# power_stub.net
KiCad netlist of a schematic drawn in EAGLE
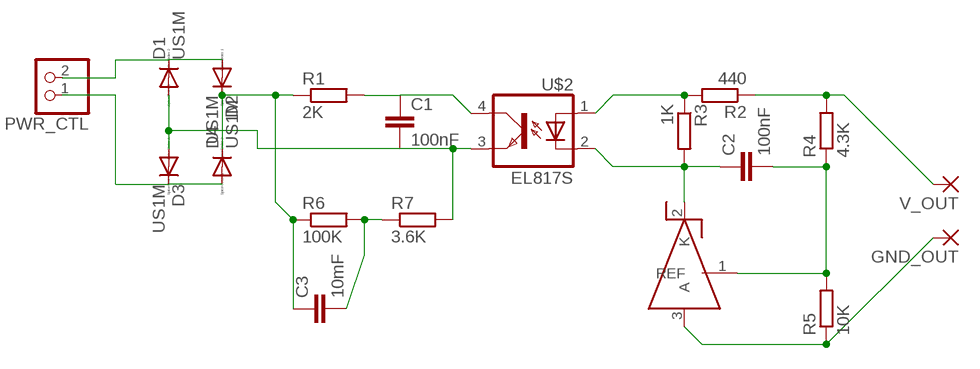
[diagram p0: schematic, sheet 1]

(export (version "E")
  (design (tool "Eeschema 10.0.6"))
  (components
    (comp (ref "C1")
      (value "100nF")
      (footprint "eagle-import:C0805")
      (libsource (lib "eagle-import") (part "C-EUC0805"))
    )
    (comp (ref "C2")
      (value "100nF")
      (footprint "eagle-import:C0805")
      (libsource (lib "eagle-import") (part "resistor_C-EUC0805"))
    )
    (comp (ref "C3")
      (value "10mF")
      (footprint "eagle-import:C0805")
      (libsource (lib "eagle-import") (part "C-EUC0805"))
    )
    (comp (ref "D1")
      (value "US1M")
      (footprint "eagle-import:DO-214AC")
      (libsource (lib "eagle-import") (part "DIODE-DO-214AC"))
    )
    (comp (ref "D2")
      (value "US1M")
      (footprint "eagle-import:DO-214AC")
      (libsource (lib "eagle-import") (part "DIODE-DO-214AC"))
    )
    (comp (ref "D3")
      (value "US1M")
      (footprint "eagle-import:DO-214AC")
      (libsource (lib "eagle-import") (part "DIODE-DO-214AC"))
    )
    (comp (ref "D4")
      (value "US1M")
      (footprint "eagle-import:DO-214AC")
      (libsource (lib "eagle-import") (part "DIODE-DO-214AC"))
    )
    (comp (ref "GND_OUT")
      (value "SMD5")
      (footprint "eagle-import:SMD2,54-5,08")
      (libsource (lib "eagle-import") (part "SMD5"))
    )
    (comp (ref "PWR_CTL")
      (value "PINHD-1X2/90")
      (footprint "eagle-import:1X02_90")
      (libsource (lib "eagle-import") (part "PINHD-1X2/90"))
    )
    (comp (ref "R1")
      (value "2K")
      (footprint "eagle-import:R0805")
      (libsource (lib "eagle-import") (part "R-EU_R0805"))
    )
    (comp (ref "R2")
      (value "440")
      (footprint "eagle-import:R0805")
      (libsource (lib "eagle-import") (part "resistor_R-EU_R0805"))
    )
    (comp (ref "R3")
      (value "1K")
      (footprint "eagle-import:R0805")
      (libsource (lib "eagle-import") (part "resistor_R-EU_R0805"))
    )
    (comp (ref "R4")
      (value "4.3K")
      (footprint "eagle-import:R0805")
      (libsource (lib "eagle-import") (part "resistor_R-EU_R0805"))
    )
    (comp (ref "R5")
      (value "10K")
      (footprint "eagle-import:R0805")
      (libsource (lib "eagle-import") (part "resistor_R-EU_R0805"))
    )
    (comp (ref "R6")
      (value "100K")
      (footprint "eagle-import:R0805")
      (libsource (lib "eagle-import") (part "R-EU_R0805"))
    )
    (comp (ref "R7")
      (value "3.6K")
      (footprint "eagle-import:R0805")
      (libsource (lib "eagle-import") (part "R-EU_R0805"))
    )
    (comp (ref "U$1")
      (value "TL431AIDBZR")
      (footprint "eagle-import:SOT23")
      (libsource (lib "eagle-import") (part "TL431AIDBZR"))
    )
    (comp (ref "U$2")
      (value "EL817S")
      (footprint "eagle-import:SMD4_L")
      (libsource (lib "eagle-import") (part "EL817S"))
    )
    (comp (ref "V_OUT")
      (value "SMD5")
      (footprint "eagle-import:SMD2,54-5,08")
      (libsource (lib "eagle-import") (part "SMD5"))
    )
  )
  (nets
    (net (code "1") (name "Net-(C3-Pad1)") (class "Default")
      (node (ref "C3") (pin "1") (pinfunction "1_1") (pintype "passive"))
      (node (ref "D2") (pin "C") (pinfunction "C_C") (pintype "passive"))
      (node (ref "D4") (pin "C") (pinfunction "C_C") (pintype "passive"))
      (node (ref "R1") (pin "1") (pinfunction "1_1") (pintype "passive"))
      (node (ref "R6") (pin "1") (pinfunction "1_1") (pintype "passive"))
    )
    (net (code "2") (name "Net-(C3-Pad2)") (class "Default")
      (node (ref "C3") (pin "2") (pinfunction "2_2") (pintype "passive"))
      (node (ref "R6") (pin "2") (pinfunction "2_2") (pintype "passive"))
      (node (ref "R7") (pin "1") (pinfunction "1_1") (pintype "passive"))
    )
    (net (code "3") (name "Net-(D1-PadC)") (class "Default")
      (node (ref "D1") (pin "C") (pinfunction "C_C") (pintype "passive"))
      (node (ref "D2") (pin "A") (pinfunction "A_A") (pintype "passive"))
      (node (ref "PWR_CTL") (pin "2") (pinfunction "2_2") (pintype "passive"))
    )
    (net (code "4") (name "Net-(D3-PadC)") (class "Default")
      (node (ref "D3") (pin "C") (pinfunction "C_C") (pintype "passive"))
      (node (ref "D4") (pin "A") (pinfunction "A_A") (pintype "passive"))
      (node (ref "PWR_CTL") (pin "1") (pinfunction "1_1") (pintype "passive"))
    )
    (net (code "5") (name "Net-(GND_OUT-P)") (class "Default")
      (node (ref "GND_OUT") (pin "1") (pinfunction "P_1") (pintype "passive"))
      (node (ref "R5") (pin "1") (pinfunction "1_1") (pintype "passive"))
      (node (ref "U$1") (pin "3") (pinfunction "A_3") (pintype "bidirectional"))
    )
    (net (code "6") (name "Net-(U$1-K)") (class "Default")
      (node (ref "C2") (pin "1") (pinfunction "1_1") (pintype "passive"))
      (node (ref "R3") (pin "2") (pinfunction "2_2") (pintype "passive"))
      (node (ref "U$1") (pin "2") (pinfunction "K_2") (pintype "bidirectional"))
      (node (ref "U$2") (pin "2") (pinfunction "C_2") (pintype "passive"))
    )
    (net (code "7") (name "Net-(U$1-REF)") (class "Default")
      (node (ref "C2") (pin "2") (pinfunction "2_2") (pintype "passive"))
      (node (ref "R4") (pin "1") (pinfunction "1_1") (pintype "passive"))
      (node (ref "R5") (pin "2") (pinfunction "2_2") (pintype "passive"))
      (node (ref "U$1") (pin "1") (pinfunction "REF_1") (pintype "bidirectional"))
    )
    (net (code "8") (name "Net-(U$2-A)") (class "Default")
      (node (ref "R2") (pin "2") (pinfunction "2_2") (pintype "passive"))
      (node (ref "R3") (pin "1") (pinfunction "1_1") (pintype "passive"))
      (node (ref "U$2") (pin "1") (pinfunction "A_1") (pintype "passive"))
    )
    (net (code "9") (name "Net-(U$2-COL)") (class "Default")
      (node (ref "C1") (pin "1") (pinfunction "1_1") (pintype "passive"))
      (node (ref "R1") (pin "2") (pinfunction "2_2") (pintype "passive"))
      (node (ref "U$2") (pin "4") (pinfunction "COL_4") (pintype "passive"))
    )
    (net (code "10") (name "Net-(U$2-EMIT)") (class "Default")
      (node (ref "C1") (pin "2") (pinfunction "2_2") (pintype "passive"))
      (node (ref "D1") (pin "A") (pinfunction "A_A") (pintype "passive"))
      (node (ref "D3") (pin "A") (pinfunction "A_A") (pintype "passive"))
      (node (ref "R7") (pin "2") (pinfunction "2_2") (pintype "passive"))
      (node (ref "U$2") (pin "3") (pinfunction "EMIT_3") (pintype "passive"))
    )
    (net (code "11") (name "Net-(V_OUT-P)") (class "Default")
      (node (ref "R2") (pin "1") (pinfunction "1_1") (pintype "passive"))
      (node (ref "R4") (pin "2") (pinfunction "2_2") (pintype "passive"))
      (node (ref "V_OUT") (pin "1") (pinfunction "P_1") (pintype "passive"))
    )
  )
)
